# RF_Connect.net
KiCad netlist of a schematic drawn in Altium Designer
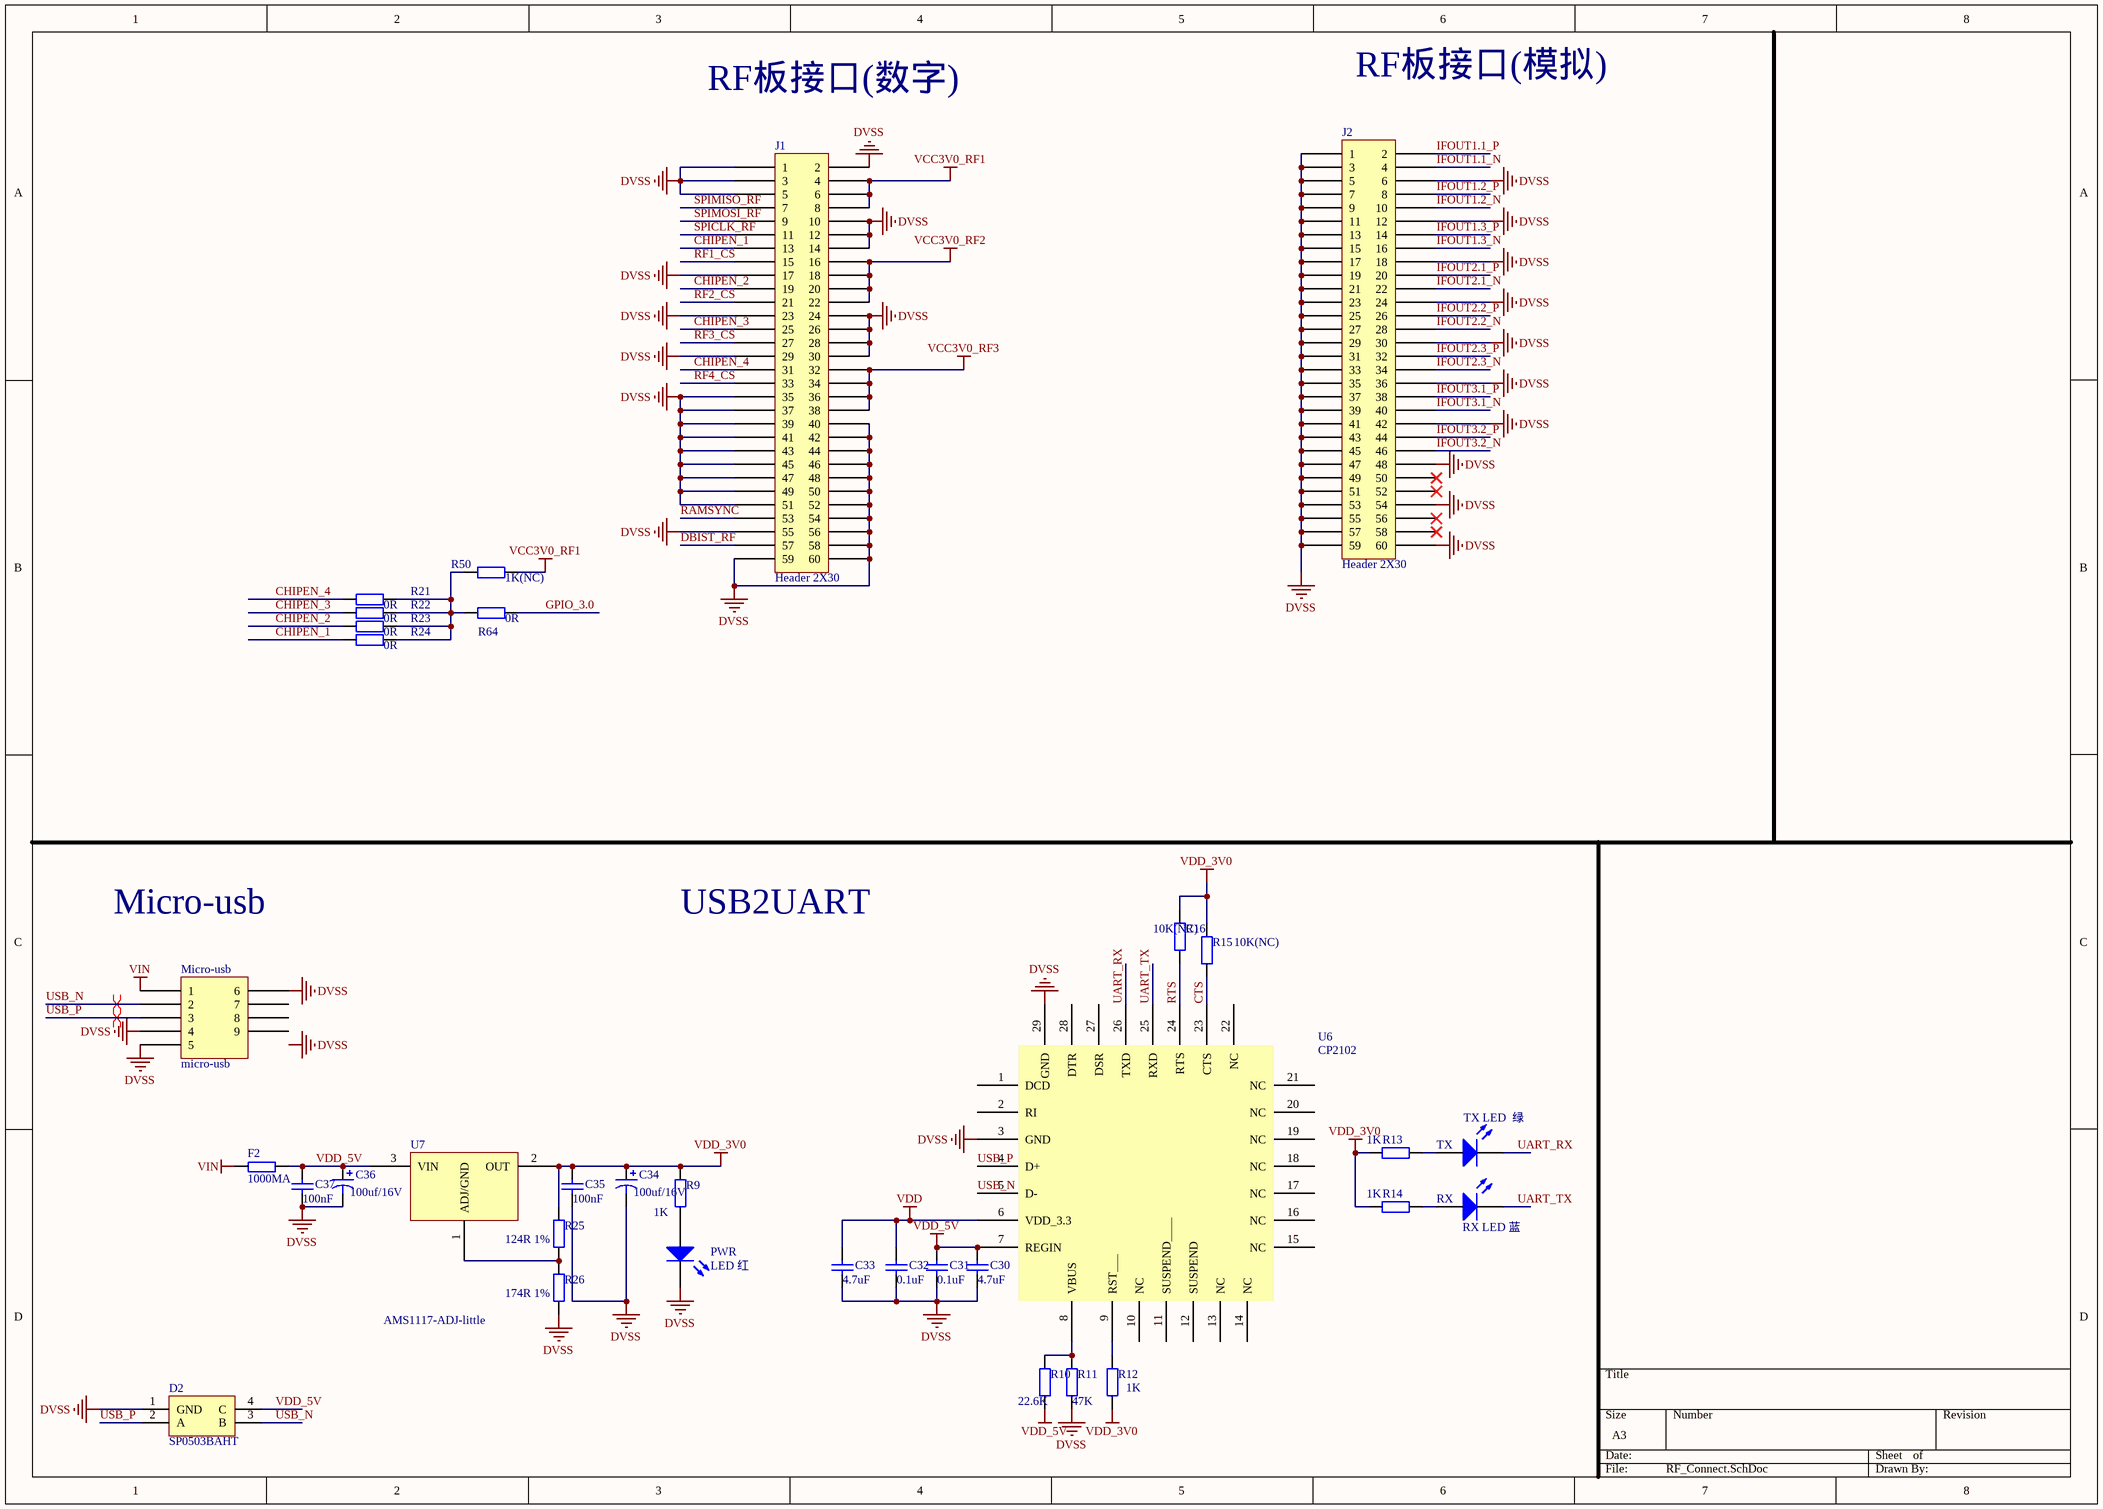
[diagram p0: RF_Connect.SchDoc]

(export (version "E")
  (design (tool "Eeschema 10.0.6"))
  (components
    (comp (ref "C30")
      (value "4.7uF")
      (footprint "R0603")
      (description "表贴电容")
      (fields (field (name "PUBLISHER") "Altium Limited"))
      (libsource (lib "Miscellaneous Devices") (part "Cap"))
    )
    (comp (ref "C31")
      (value "0.1uF")
      (footprint "R0603")
      (description "表贴电容")
      (fields (field (name "PUBLISHER") "Altium Limited"))
      (libsource (lib "Miscellaneous Devices") (part "Cap"))
    )
    (comp (ref "C32")
      (value "0.1uF")
      (footprint "R0603")
      (description "表贴电容")
      (fields (field (name "PUBLISHER") "Altium Limited"))
      (libsource (lib "Miscellaneous Devices") (part "Cap"))
    )
    (comp (ref "C33")
      (value "4.7uF")
      (footprint "R0603")
      (description "表贴电容")
      (fields (field (name "PUBLISHER") "Altium Limited"))
      (libsource (lib "Miscellaneous Devices") (part "Cap"))
    )
    (comp (ref "C34")
      (value "100uf/16V")
      (footprint "TAN3528")
      (description "tan3528 100uf/16V")
      (fields (field (name "PUBLISHER") "Altium Limited"))
      (libsource (lib "Miscellaneous Devices") (part "Cap Pol1"))
    )
    (comp (ref "C35")
      (value "100nF")
      (footprint "R0603")
      (fields (field (name "PUBLISHER") "Altium Limited"))
      (libsource (lib "SKY1311T-READER-V1.0_1") (part "Cap"))
    )
    (comp (ref "C36")
      (value "100uf/16V")
      (footprint "TAN3528")
      (description "tan3528 100uf/16V")
      (fields (field (name "PUBLISHER") "Altium Limited"))
      (libsource (lib "Miscellaneous Devices") (part "Cap Pol1"))
    )
    (comp (ref "C37")
      (value "100nF")
      (footprint "R0603")
      (fields (field (name "PUBLISHER") "Altium Limited"))
      (libsource (lib "SKY1311T-READER-V1.0_1") (part "Cap"))
    )
    (comp (ref "D2")
      (value "SP0503BAHT")
      (footprint "SOT143")
      (description "表贴芯片")
      (libsource (lib "Core_Moudle") (part "SP0503BAHT"))
    )
    (comp (ref "F2")
      (value "1000MA")
      (footprint "0805")
      (description "表贴保险")
      (libsource (lib "北极星STM32F750&H750底板封装库") (part "R_1"))
    )
    (comp (ref "J1")
      (value "Header 2X30")
      (footprint "60pin_0.8mm")
      (description "2x30 ， 60P， 0.8mm ，立贴 ，母")
      (libsource (lib "SKY32B750_OSPI_EVB1_V2.0") (part "Header 2X30"))
    )
    (comp (ref "J2")
      (value "Header 2X30")
      (footprint "60pin_0.8mm")
      (description "2x30 ， 60P， 0.8mm ，立贴 ，母")
      (libsource (lib "SKY32B750_OSPI_EVB1_V2.0") (part "Header 2X30"))
    )
    (comp (ref "Micro-usb")
      (value "micro-usb")
      (footprint "Micro-B")
      (description "Micro-B")
      (libsource (lib "SKY32B750_OSPI_EVB1_V3.0") (part "Micro-B"))
    )
    (comp (ref "PWR")
      (value "LED 红")
      (footprint "LC-0603_LED_S4")
      (description "表贴LED管")
      (libsource (lib "MyMiscellaneousDevice") (part "LED-SMT"))
    )
    (comp (ref "R9")
      (value "1K")
      (footprint "R0603")
      (description "表贴电阻")
      (fields (field (name "PUBLISHER") "Altium Limited"))
      (libsource (lib "") (part "Res2_1"))
    )
    (comp (ref "R10")
      (value "22.6K")
      (footprint "R0603")
      (description "表贴电阻")
      (fields (field (name "PUBLISHER") "Altium Limited"))
      (libsource (lib "") (part "Res2_1"))
    )
    (comp (ref "R11")
      (value "47K")
      (footprint "R0603")
      (description "表贴电阻")
      (fields (field (name "PUBLISHER") "Altium Limited"))
      (libsource (lib "") (part "Res2_1"))
    )
    (comp (ref "R12")
      (value "1K")
      (footprint "R0603")
      (description "表贴电阻")
      (fields (field (name "PUBLISHER") "Altium Limited"))
      (libsource (lib "") (part "Res2_1"))
    )
    (comp (ref "R13")
      (value "1K")
      (footprint "R0603")
      (description "表贴电阻")
      (fields (field (name "PUBLISHER") "Altium Limited"))
      (libsource (lib "Miscellaneous Devices") (part "Res2"))
    )
    (comp (ref "R14")
      (value "1K")
      (footprint "R0603")
      (description "表贴电阻")
      (fields (field (name "PUBLISHER") "Altium Limited"))
      (libsource (lib "Miscellaneous Devices") (part "Res2"))
    )
    (comp (ref "R15")
      (value "10K(NC)")
      (footprint "R0603")
      (description "表贴电阻")
      (fields (field (name "PUBLISHER") "Altium Limited"))
      (libsource (lib "") (part "Res2_1"))
    )
    (comp (ref "R16")
      (value "10K(NC)")
      (footprint "R0603")
      (description "表贴电阻")
      (fields (field (name "PUBLISHER") "Altium Limited"))
      (libsource (lib "") (part "Res2_1"))
    )
    (comp (ref "R21")
      (value "0R")
      (footprint "R0603")
      (description "Resistor")
      (fields
        (field (name "MANUFACTURER") "Generic Components")
        (field (name "PUBLISHER") "Altium Hobart Technology Centre")
      )
      (libsource (lib "Core_Moudle") (part "Res2"))
    )
    (comp (ref "R22")
      (value "0R")
      (footprint "R0603")
      (description "Resistor")
      (fields
        (field (name "MANUFACTURER") "Generic Components")
        (field (name "PUBLISHER") "Altium Hobart Technology Centre")
      )
      (libsource (lib "Core_Moudle") (part "Res2"))
    )
    (comp (ref "R23")
      (value "0R")
      (footprint "R0603")
      (description "Resistor")
      (fields
        (field (name "MANUFACTURER") "Generic Components")
        (field (name "PUBLISHER") "Altium Hobart Technology Centre")
      )
      (libsource (lib "Core_Moudle") (part "Res2"))
    )
    (comp (ref "R24")
      (value "0R")
      (footprint "R0603")
      (description "Resistor")
      (fields
        (field (name "MANUFACTURER") "Generic Components")
        (field (name "PUBLISHER") "Altium Hobart Technology Centre")
      )
      (libsource (lib "Core_Moudle") (part "Res2"))
    )
    (comp (ref "R25")
      (value "124R 1%")
      (footprint "R0603")
      (fields (field (name "PUBLISHER") "Altium Limited"))
      (libsource (lib "") (part "Res2_2"))
    )
    (comp (ref "R26")
      (value "174R 1%")
      (footprint "R0603")
      (fields (field (name "PUBLISHER") "Altium Limited"))
      (libsource (lib "") (part "Res2_2"))
    )
    (comp (ref "R50")
      (value "1K(NC)")
      (footprint "R0603")
      (description "Resistor")
      (fields
        (field (name "MANUFACTURER") "Generic Components")
        (field (name "PUBLISHER") "Altium Hobart Technology Centre")
      )
      (libsource (lib "Core_Moudle") (part "Res2"))
    )
    (comp (ref "R64")
      (value "0R")
      (footprint "R0603")
      (description "Resistor")
      (fields
        (field (name "MANUFACTURER") "Generic Components")
        (field (name "PUBLISHER") "Altium Hobart Technology Centre")
      )
      (libsource (lib "Core_Moudle") (part "Res2"))
    )
    (comp (ref "RX")
      (value "RX LED 蓝")
      (footprint "LC-0603_LED_S4")
      (description "表贴LED管")
      (libsource (lib "MyMiscellaneousDevice") (part "LED-SMT"))
    )
    (comp (ref "TX")
      (value "TX LED  绿")
      (footprint "LC-0603_LED_S4")
      (description "表贴LED管")
      (libsource (lib "MyMiscellaneousDevice") (part "LED-SMT"))
    )
    (comp (ref "U6")
      (value "CP2102")
      (footprint "QFN28N5X5P0.5E3.35")
      (description "表贴芯片")
      (libsource (lib "USBTOUART") (part "Component_2"))
    )
    (comp (ref "U7")
      (value "AMS1117-ADJ-little")
      (footprint "LDO-SOT-89-3")
      (description "AMS1117-ADJ-little ，SOT-89-3")
      (libsource (lib "SKY32B750_OSPI_EVB1_V2.0") (part "AMS1117-ADJ-little"))
    )
  )
  (nets
    (net (code "1") (name "/CHIPEN_1") (class "Default")
      (node (ref "J1") (pin "13") (pinfunction "13_13") (pintype "passive"))
      (node (ref "R24") (pin "1") (pinfunction "1_1") (pintype "passive"))
    )
    (net (code "2") (name "/CHIPEN_2") (class "Default")
      (node (ref "J1") (pin "19") (pinfunction "19_19") (pintype "passive"))
      (node (ref "R23") (pin "1") (pinfunction "1_1") (pintype "passive"))
    )
    (net (code "3") (name "/CHIPEN_3") (class "Default")
      (node (ref "J1") (pin "25") (pinfunction "25_25") (pintype "passive"))
      (node (ref "R22") (pin "1") (pinfunction "1_1") (pintype "passive"))
    )
    (net (code "4") (name "/CHIPEN_4") (class "Default")
      (node (ref "J1") (pin "31") (pinfunction "31_31") (pintype "passive"))
      (node (ref "R21") (pin "1") (pinfunction "1_1") (pintype "passive"))
    )
    (net (code "5") (name "/CTS") (class "Default")
      (node (ref "R15") (pin "2") (pinfunction "2_2") (pintype "passive"))
      (node (ref "U6") (pin "23") (pinfunction "CTS_23") (pintype "open_collector"))
    )
    (net (code "6") (name "/DBIST_RF") (class "Default")
      (node (ref "J1") (pin "57") (pinfunction "57_57") (pintype "passive"))
    )
    (net (code "7") (name "/GPIO_3.0") (class "Default")
      (node (ref "R64") (pin "2") (pinfunction "2_2") (pintype "passive"))
    )
    (net (code "8") (name "/IFOUT1.1_N") (class "Default")
      (node (ref "J2") (pin "4") (pinfunction "4_4") (pintype "passive"))
    )
    (net (code "9") (name "/IFOUT1.1_P") (class "Default")
      (node (ref "J2") (pin "2") (pinfunction "2_2") (pintype "passive"))
    )
    (net (code "10") (name "/IFOUT1.2_N") (class "Default")
      (node (ref "J2") (pin "10") (pinfunction "10_10") (pintype "passive"))
    )
    (net (code "11") (name "/IFOUT1.2_P") (class "Default")
      (node (ref "J2") (pin "8") (pinfunction "8_8") (pintype "passive"))
    )
    (net (code "12") (name "/IFOUT1.3_N") (class "Default")
      (node (ref "J2") (pin "16") (pinfunction "16_16") (pintype "passive"))
    )
    (net (code "13") (name "/IFOUT1.3_P") (class "Default")
      (node (ref "J2") (pin "14") (pinfunction "14_14") (pintype "passive"))
    )
    (net (code "14") (name "/IFOUT2.1_N") (class "Default")
      (node (ref "J2") (pin "22") (pinfunction "22_22") (pintype "passive"))
    )
    (net (code "15") (name "/IFOUT2.1_P") (class "Default")
      (node (ref "J2") (pin "20") (pinfunction "20_20") (pintype "passive"))
    )
    (net (code "16") (name "/IFOUT2.2_N") (class "Default")
      (node (ref "J2") (pin "28") (pinfunction "28_28") (pintype "passive"))
    )
    (net (code "17") (name "/IFOUT2.2_P") (class "Default")
      (node (ref "J2") (pin "26") (pinfunction "26_26") (pintype "passive"))
    )
    (net (code "18") (name "/IFOUT2.3_N") (class "Default")
      (node (ref "J2") (pin "34") (pinfunction "34_34") (pintype "passive"))
    )
    (net (code "19") (name "/IFOUT2.3_P") (class "Default")
      (node (ref "J2") (pin "32") (pinfunction "32_32") (pintype "passive"))
    )
    (net (code "20") (name "/IFOUT3.1_N") (class "Default")
      (node (ref "J2") (pin "40") (pinfunction "40_40") (pintype "passive"))
    )
    (net (code "21") (name "/IFOUT3.1_P") (class "Default")
      (node (ref "J2") (pin "38") (pinfunction "38_38") (pintype "passive"))
    )
    (net (code "22") (name "/IFOUT3.2_N") (class "Default")
      (node (ref "J2") (pin "46") (pinfunction "46_46") (pintype "passive"))
    )
    (net (code "23") (name "/IFOUT3.2_P") (class "Default")
      (node (ref "J2") (pin "44") (pinfunction "44_44") (pintype "passive"))
    )
    (net (code "24") (name "/RAMSYNC") (class "Default")
      (node (ref "J1") (pin "53") (pinfunction "53_53") (pintype "passive"))
    )
    (net (code "25") (name "/RF1_CS") (class "Default")
      (node (ref "J1") (pin "15") (pinfunction "15_15") (pintype "passive"))
    )
    (net (code "26") (name "/RF2_CS") (class "Default")
      (node (ref "J1") (pin "21") (pinfunction "21_21") (pintype "passive"))
    )
    (net (code "27") (name "/RF3_CS") (class "Default")
      (node (ref "J1") (pin "27") (pinfunction "27_27") (pintype "passive"))
    )
    (net (code "28") (name "/RF4_CS") (class "Default")
      (node (ref "J1") (pin "33") (pinfunction "33_33") (pintype "passive"))
    )
    (net (code "29") (name "/RTS") (class "Default")
      (node (ref "R16") (pin "2") (pinfunction "2_2") (pintype "passive"))
      (node (ref "U6") (pin "24") (pinfunction "RTS_24") (pintype "open_collector"))
    )
    (net (code "30") (name "/SPICLK_RF") (class "Default")
      (node (ref "J1") (pin "11") (pinfunction "11_11") (pintype "passive"))
    )
    (net (code "31") (name "/SPIMISO_RF") (class "Default")
      (node (ref "J1") (pin "7") (pinfunction "7_7") (pintype "passive"))
    )
    (net (code "32") (name "/SPIMOSI_RF") (class "Default")
      (node (ref "J1") (pin "9") (pinfunction "9_9") (pintype "passive"))
    )
    (net (code "33") (name "/UART_RX") (class "Default")
      (node (ref "TX") (pin "2") (pinfunction "K_2") (pintype "passive"))
      (node (ref "U6") (pin "26") (pinfunction "TXD_26") (pintype "open_collector"))
    )
    (net (code "34") (name "/UART_TX") (class "Default")
      (node (ref "RX") (pin "2") (pinfunction "K_2") (pintype "passive"))
      (node (ref "U6") (pin "25") (pinfunction "RXD_25") (pintype "open_collector"))
    )
    (net (code "35") (name "/USB_N") (class "Default")
      (node (ref "D2") (pin "3") (pinfunction "B_3") (pintype "passive"))
      (node (ref "Micro-usb") (pin "2") (pinfunction "2_2") (pintype "passive"))
      (node (ref "U6") (pin "5") (pinfunction "D-_5") (pintype "open_collector"))
    )
    (net (code "36") (name "/USB_P") (class "Default")
      (node (ref "D2") (pin "2") (pinfunction "A_2") (pintype "passive"))
      (node (ref "Micro-usb") (pin "3") (pinfunction "3_3") (pintype "passive"))
      (node (ref "U6") (pin "4") (pinfunction "D+_4") (pintype "open_collector"))
    )
    (net (code "37") (name "DVSS") (class "Default")
      (node (ref "C30") (pin "2") (pinfunction "2_2") (pintype "passive"))
      (node (ref "C31") (pin "2") (pinfunction "2_2") (pintype "passive"))
      (node (ref "C32") (pin "2") (pinfunction "2_2") (pintype "passive"))
      (node (ref "C33") (pin "2") (pinfunction "2_2") (pintype "passive"))
      (node (ref "C34") (pin "2") (pinfunction "2_2") (pintype "passive"))
      (node (ref "C35") (pin "1") (pinfunction "1_1") (pintype "passive"))
      (node (ref "C36") (pin "2") (pinfunction "2_2") (pintype "passive"))
      (node (ref "C37") (pin "1") (pinfunction "1_1") (pintype "passive"))
      (node (ref "D2") (pin "1") (pinfunction "GND_1") (pintype "passive"))
      (node (ref "J1") (pin "1") (pinfunction "1_1") (pintype "passive"))
      (node (ref "J1") (pin "10") (pinfunction "10_10") (pintype "passive"))
      (node (ref "J1") (pin "12") (pinfunction "12_12") (pintype "passive"))
      (node (ref "J1") (pin "14") (pinfunction "14_14") (pintype "passive"))
      (node (ref "J1") (pin "17") (pinfunction "17_17") (pintype "passive"))
      (node (ref "J1") (pin "2") (pinfunction "2_2") (pintype "passive"))
      (node (ref "J1") (pin "23") (pinfunction "23_23") (pintype "passive"))
      (node (ref "J1") (pin "24") (pinfunction "24_24") (pintype "passive"))
      (node (ref "J1") (pin "26") (pinfunction "26_26") (pintype "passive"))
      (node (ref "J1") (pin "28") (pinfunction "28_28") (pintype "passive"))
      (node (ref "J1") (pin "29") (pinfunction "29_29") (pintype "passive"))
      (node (ref "J1") (pin "3") (pinfunction "3_3") (pintype "passive"))
      (node (ref "J1") (pin "30") (pinfunction "30_30") (pintype "passive"))
      (node (ref "J1") (pin "35") (pinfunction "35_35") (pintype "passive"))
      (node (ref "J1") (pin "37") (pinfunction "37_37") (pintype "passive"))
      (node (ref "J1") (pin "39") (pinfunction "39_39") (pintype "passive"))
      (node (ref "J1") (pin "40") (pinfunction "40_40") (pintype "passive"))
      (node (ref "J1") (pin "41") (pinfunction "41_41") (pintype "passive"))
      (node (ref "J1") (pin "42") (pinfunction "42_42") (pintype "passive"))
      (node (ref "J1") (pin "43") (pinfunction "43_43") (pintype "passive"))
      (node (ref "J1") (pin "44") (pinfunction "44_44") (pintype "passive"))
      (node (ref "J1") (pin "45") (pinfunction "45_45") (pintype "passive"))
      (node (ref "J1") (pin "46") (pinfunction "46_46") (pintype "passive"))
      (node (ref "J1") (pin "47") (pinfunction "47_47") (pintype "passive"))
      (node (ref "J1") (pin "48") (pinfunction "48_48") (pintype "passive"))
      (node (ref "J1") (pin "49") (pinfunction "49_49") (pintype "passive"))
      (node (ref "J1") (pin "5") (pinfunction "5_5") (pintype "passive"))
      (node (ref "J1") (pin "50") (pinfunction "50_50") (pintype "passive"))
      (node (ref "J1") (pin "51") (pinfunction "51_51") (pintype "passive"))
      (node (ref "J1") (pin "52") (pinfunction "52_52") (pintype "passive"))
      (node (ref "J1") (pin "54") (pinfunction "54_54") (pintype "passive"))
      (node (ref "J1") (pin "55") (pinfunction "55_55") (pintype "passive"))
      (node (ref "J1") (pin "56") (pinfunction "56_56") (pintype "passive"))
      (node (ref "J1") (pin "58") (pinfunction "58_58") (pintype "passive"))
      (node (ref "J1") (pin "59") (pinfunction "59_59") (pintype "passive"))
      (node (ref "J1") (pin "60") (pinfunction "60_60") (pintype "passive"))
      (node (ref "J2") (pin "1") (pinfunction "1_1") (pintype "passive"))
      (node (ref "J2") (pin "11") (pinfunction "11_11") (pintype "passive"))
      (node (ref "J2") (pin "12") (pinfunction "12_12") (pintype "passive"))
      (node (ref "J2") (pin "13") (pinfunction "13_13") (pintype "passive"))
      (node (ref "J2") (pin "15") (pinfunction "15_15") (pintype "passive"))
      (node (ref "J2") (pin "17") (pinfunction "17_17") (pintype "passive"))
      (node (ref "J2") (pin "18") (pinfunction "18_18") (pintype "passive"))
      (node (ref "J2") (pin "19") (pinfunction "19_19") (pintype "passive"))
      (node (ref "J2") (pin "21") (pinfunction "21_21") (pintype "passive"))
      (node (ref "J2") (pin "23") (pinfunction "23_23") (pintype "passive"))
      (node (ref "J2") (pin "24") (pinfunction "24_24") (pintype "passive"))
      (node (ref "J2") (pin "25") (pinfunction "25_25") (pintype "passive"))
      (node (ref "J2") (pin "27") (pinfunction "27_27") (pintype "passive"))
      (node (ref "J2") (pin "29") (pinfunction "29_29") (pintype "passive"))
      (node (ref "J2") (pin "3") (pinfunction "3_3") (pintype "passive"))
      (node (ref "J2") (pin "30") (pinfunction "30_30") (pintype "passive"))
      (node (ref "J2") (pin "31") (pinfunction "31_31") (pintype "passive"))
      (node (ref "J2") (pin "33") (pinfunction "33_33") (pintype "passive"))
      (node (ref "J2") (pin "35") (pinfunction "35_35") (pintype "passive"))
      (node (ref "J2") (pin "36") (pinfunction "36_36") (pintype "passive"))
      (node (ref "J2") (pin "37") (pinfunction "37_37") (pintype "passive"))
      (node (ref "J2") (pin "39") (pinfunction "39_39") (pintype "passive"))
      (node (ref "J2") (pin "41") (pinfunction "41_41") (pintype "passive"))
      (node (ref "J2") (pin "42") (pinfunction "42_42") (pintype "passive"))
      (node (ref "J2") (pin "43") (pinfunction "43_43") (pintype "passive"))
      (node (ref "J2") (pin "45") (pinfunction "45_45") (pintype "passive"))
      (node (ref "J2") (pin "47") (pinfunction "47_47") (pintype "passive"))
      (node (ref "J2") (pin "48") (pinfunction "48_48") (pintype "passive"))
      (node (ref "J2") (pin "49") (pinfunction "49_49") (pintype "passive"))
      (node (ref "J2") (pin "5") (pinfunction "5_5") (pintype "passive"))
      (node (ref "J2") (pin "51") (pinfunction "51_51") (pintype "passive"))
      (node (ref "J2") (pin "53") (pinfunction "53_53") (pintype "passive"))
      (node (ref "J2") (pin "54") (pinfunction "54_54") (pintype "passive"))
      (node (ref "J2") (pin "55") (pinfunction "55_55") (pintype "passive"))
      (node (ref "J2") (pin "57") (pinfunction "57_57") (pintype "passive"))
      (node (ref "J2") (pin "59") (pinfunction "59_59") (pintype "passive"))
      (node (ref "J2") (pin "6") (pinfunction "6_6") (pintype "passive"))
      (node (ref "J2") (pin "60") (pinfunction "60_60") (pintype "passive"))
      (node (ref "J2") (pin "7") (pinfunction "7_7") (pintype "passive"))
      (node (ref "J2") (pin "9") (pinfunction "9_9") (pintype "passive"))
      (node (ref "Micro-usb") (pin "4") (pinfunction "4_4") (pintype "passive"))
      (node (ref "Micro-usb") (pin "5") (pinfunction "5_5") (pintype "passive"))
      (node (ref "Micro-usb") (pin "6") (pinfunction "6_6") (pintype "passive"))
      (node (ref "PWR") (pin "2") (pinfunction "K_2") (pintype "passive"))
      (node (ref "R11") (pin "2") (pinfunction "2_2") (pintype "passive"))
      (node (ref "R26") (pin "1") (pinfunction "1_1") (pintype "passive"))
      (node (ref "U6") (pin "29") (pinfunction "GND_29") (pintype "passive"))
      (node (ref "U6") (pin "3") (pinfunction "GND_3") (pintype "open_collector"))
    )
    (net (code "38") (name "Net-(PWR-A)") (class "Default")
      (node (ref "PWR") (pin "1") (pinfunction "A_1") (pintype "passive"))
      (node (ref "R9") (pin "2") (pinfunction "2_2") (pintype "passive"))
    )
    (net (code "39") (name "Net-(R21-Pad2)") (class "Default")
      (node (ref "R21") (pin "2") (pinfunction "2_2") (pintype "passive"))
      (node (ref "R22") (pin "2") (pinfunction "2_2") (pintype "passive"))
      (node (ref "R23") (pin "2") (pinfunction "2_2") (pintype "passive"))
      (node (ref "R24") (pin "2") (pinfunction "2_2") (pintype "passive"))
      (node (ref "R50") (pin "1") (pinfunction "1_1") (pintype "passive"))
      (node (ref "R64") (pin "1") (pinfunction "1_1") (pintype "passive"))
    )
    (net (code "40") (name "Net-(RX-A)") (class "Default")
      (node (ref "R14") (pin "1") (pinfunction "1_1") (pintype "passive"))
      (node (ref "RX") (pin "1") (pinfunction "A_1") (pintype "passive"))
    )
    (net (code "41") (name "Net-(TX-A)") (class "Default")
      (node (ref "R13") (pin "1") (pinfunction "1_1") (pintype "passive"))
      (node (ref "TX") (pin "1") (pinfunction "A_1") (pintype "passive"))
    )
    (net (code "42") (name "Net-(U6-RST___)") (class "Default")
      (node (ref "R12") (pin "1") (pinfunction "1_1") (pintype "passive"))
      (node (ref "U6") (pin "9") (pinfunction "RST____9") (pintype "open_collector"))
    )
    (net (code "43") (name "Net-(U6-VBUS)") (class "Default")
      (node (ref "R10") (pin "1") (pinfunction "1_1") (pintype "passive"))
      (node (ref "R11") (pin "1") (pinfunction "1_1") (pintype "passive"))
      (node (ref "U6") (pin "8") (pinfunction "VBUS_8") (pintype "open_collector"))
    )
    (net (code "44") (name "Net-(U7-ADJ{slash}GND)") (class "Default")
      (node (ref "R25") (pin "1") (pinfunction "1_1") (pintype "passive"))
      (node (ref "R26") (pin "2") (pinfunction "2_2") (pintype "passive"))
      (node (ref "U7") (pin "1") (pinfunction "ADJ/GND_1") (pintype "passive"))
    )
    (net (code "45") (name "VCC3V0_RF1") (class "Default")
      (node (ref "J1") (pin "4") (pinfunction "4_4") (pintype "passive"))
      (node (ref "J1") (pin "6") (pinfunction "6_6") (pintype "passive"))
      (node (ref "J1") (pin "8") (pinfunction "8_8") (pintype "passive"))
      (node (ref "R50") (pin "2") (pinfunction "2_2") (pintype "passive"))
    )
    (net (code "46") (name "VCC3V0_RF2") (class "Default")
      (node (ref "J1") (pin "16") (pinfunction "16_16") (pintype "passive"))
      (node (ref "J1") (pin "18") (pinfunction "18_18") (pintype "passive"))
      (node (ref "J1") (pin "20") (pinfunction "20_20") (pintype "passive"))
      (node (ref "J1") (pin "22") (pinfunction "22_22") (pintype "passive"))
    )
    (net (code "47") (name "VCC3V0_RF3") (class "Default")
      (node (ref "J1") (pin "32") (pinfunction "32_32") (pintype "passive"))
      (node (ref "J1") (pin "34") (pinfunction "34_34") (pintype "passive"))
      (node (ref "J1") (pin "36") (pinfunction "36_36") (pintype "passive"))
      (node (ref "J1") (pin "38") (pinfunction "38_38") (pintype "passive"))
    )
    (net (code "48") (name "VDD") (class "Default")
      (node (ref "C32") (pin "1") (pinfunction "1_1") (pintype "passive"))
      (node (ref "C33") (pin "1") (pinfunction "1_1") (pintype "passive"))
      (node (ref "U6") (pin "6") (pinfunction "VDD_3.3_6") (pintype "open_collector"))
    )
    (net (code "49") (name "VDD_3V0") (class "Default")
      (node (ref "C34") (pin "1") (pinfunction "1_1") (pintype "passive"))
      (node (ref "C35") (pin "2") (pinfunction "2_2") (pintype "passive"))
      (node (ref "R12") (pin "2") (pinfunction "2_2") (pintype "passive"))
      (node (ref "R13") (pin "2") (pinfunction "2_2") (pintype "passive"))
      (node (ref "R14") (pin "2") (pinfunction "2_2") (pintype "passive"))
      (node (ref "R15") (pin "1") (pinfunction "1_1") (pintype "passive"))
      (node (ref "R16") (pin "1") (pinfunction "1_1") (pintype "passive"))
      (node (ref "R25") (pin "2") (pinfunction "2_2") (pintype "passive"))
      (node (ref "R9") (pin "1") (pinfunction "1_1") (pintype "passive"))
      (node (ref "U7") (pin "2") (pinfunction "OUT_2") (pintype "passive"))
    )
    (net (code "50") (name "VDD_5V") (class "Default")
      (node (ref "C30") (pin "1") (pinfunction "1_1") (pintype "passive"))
      (node (ref "C31") (pin "1") (pinfunction "1_1") (pintype "passive"))
      (node (ref "C36") (pin "1") (pinfunction "1_1") (pintype "passive"))
      (node (ref "C37") (pin "2") (pinfunction "2_2") (pintype "passive"))
      (node (ref "D2") (pin "4") (pinfunction "C_4") (pintype "passive"))
      (node (ref "F2") (pin "2") (pintype "passive"))
      (node (ref "R10") (pin "2") (pinfunction "2_2") (pintype "passive"))
      (node (ref "U6") (pin "7") (pinfunction "REGIN_7") (pintype "open_collector"))
      (node (ref "U7") (pin "3") (pinfunction "VIN_3") (pintype "passive"))
    )
    (net (code "51") (name "VIN") (class "Default")
      (node (ref "F2") (pin "1") (pintype "passive"))
      (node (ref "Micro-usb") (pin "1") (pinfunction "1_1") (pintype "passive"))
    )
    (net (code "52") (name "unconnected-(J2-Pad50)") (class "Default")
      (node (ref "J2") (pin "50") (pinfunction "50_50") (pintype "passive+no_connect"))
    )
    (net (code "53") (name "unconnected-(J2-Pad52)") (class "Default")
      (node (ref "J2") (pin "52") (pinfunction "52_52") (pintype "passive+no_connect"))
    )
    (net (code "54") (name "unconnected-(J2-Pad56)") (class "Default")
      (node (ref "J2") (pin "56") (pinfunction "56_56") (pintype "passive+no_connect"))
    )
    (net (code "55") (name "unconnected-(J2-Pad58)") (class "Default")
      (node (ref "J2") (pin "58") (pinfunction "58_58") (pintype "passive+no_connect"))
    )
    (net (code "56") (name "unconnected-(Micro-usb-Pad7)") (class "Default")
      (node (ref "Micro-usb") (pin "7") (pinfunction "7_7") (pintype "passive"))
    )
    (net (code "57") (name "unconnected-(Micro-usb-Pad8)") (class "Default")
      (node (ref "Micro-usb") (pin "8") (pinfunction "8_8") (pintype "passive"))
    )
    (net (code "58") (name "unconnected-(Micro-usb-Pad9)") (class "Default")
      (node (ref "Micro-usb") (pin "9") (pinfunction "9_9") (pintype "passive"))
    )
    (net (code "59") (name "unconnected-(U6-DCD-Pad1)") (class "Default")
      (node (ref "U6") (pin "1") (pinfunction "DCD_1") (pintype "open_collector"))
    )
    (net (code "60") (name "unconnected-(U6-DSR-Pad27)") (class "Default")
      (node (ref "U6") (pin "27") (pinfunction "DSR_27") (pintype "open_collector"))
    )
    (net (code "61") (name "unconnected-(U6-DTR-Pad28)") (class "Default")
      (node (ref "U6") (pin "28") (pinfunction "DTR_28") (pintype "open_collector"))
    )
    (net (code "62") (name "unconnected-(U6-NC-Pad10)") (class "Default")
      (node (ref "U6") (pin "10") (pinfunction "NC_10") (pintype "open_collector"))
    )
    (net (code "63") (name "unconnected-(U6-NC-Pad13)") (class "Default")
      (node (ref "U6") (pin "13") (pinfunction "NC_13") (pintype "open_collector"))
    )
    (net (code "64") (name "unconnected-(U6-NC-Pad14)") (class "Default")
      (node (ref "U6") (pin "14") (pinfunction "NC_14") (pintype "open_collector"))
    )
    (net (code "65") (name "unconnected-(U6-NC-Pad15)") (class "Default")
      (node (ref "U6") (pin "15") (pinfunction "NC_15") (pintype "open_collector"))
    )
    (net (code "66") (name "unconnected-(U6-NC-Pad16)") (class "Default")
      (node (ref "U6") (pin "16") (pinfunction "NC_16") (pintype "open_collector"))
    )
    (net (code "67") (name "unconnected-(U6-NC-Pad17)") (class "Default")
      (node (ref "U6") (pin "17") (pinfunction "NC_17") (pintype "open_collector"))
    )
    (net (code "68") (name "unconnected-(U6-NC-Pad18)") (class "Default")
      (node (ref "U6") (pin "18") (pinfunction "NC_18") (pintype "open_collector"))
    )
    (net (code "69") (name "unconnected-(U6-NC-Pad19)") (class "Default")
      (node (ref "U6") (pin "19") (pinfunction "NC_19") (pintype "open_collector"))
    )
    (net (code "70") (name "unconnected-(U6-NC-Pad20)") (class "Default")
      (node (ref "U6") (pin "20") (pinfunction "NC_20") (pintype "open_collector"))
    )
    (net (code "71") (name "unconnected-(U6-NC-Pad21)") (class "Default")
      (node (ref "U6") (pin "21") (pinfunction "NC_21") (pintype "open_collector"))
    )
    (net (code "72") (name "unconnected-(U6-NC-Pad22)") (class "Default")
      (node (ref "U6") (pin "22") (pinfunction "NC_22") (pintype "open_collector"))
    )
    (net (code "73") (name "unconnected-(U6-RI-Pad2)") (class "Default")
      (node (ref "U6") (pin "2") (pinfunction "RI_2") (pintype "open_collector"))
    )
    (net (code "74") (name "unconnected-(U6-SUSPEND-Pad12)") (class "Default")
      (node (ref "U6") (pin "12") (pinfunction "SUSPEND_12") (pintype "open_collector"))
    )
    (net (code "75") (name "unconnected-(U6-SUSPEND____-Pad11)") (class "Default")
      (node (ref "U6") (pin "11") (pinfunction "SUSPEND_____11") (pintype "open_collector"))
    )
  )
)
